# cc1110.net
KiCad netlist of a schematic drawn in Altium Designer
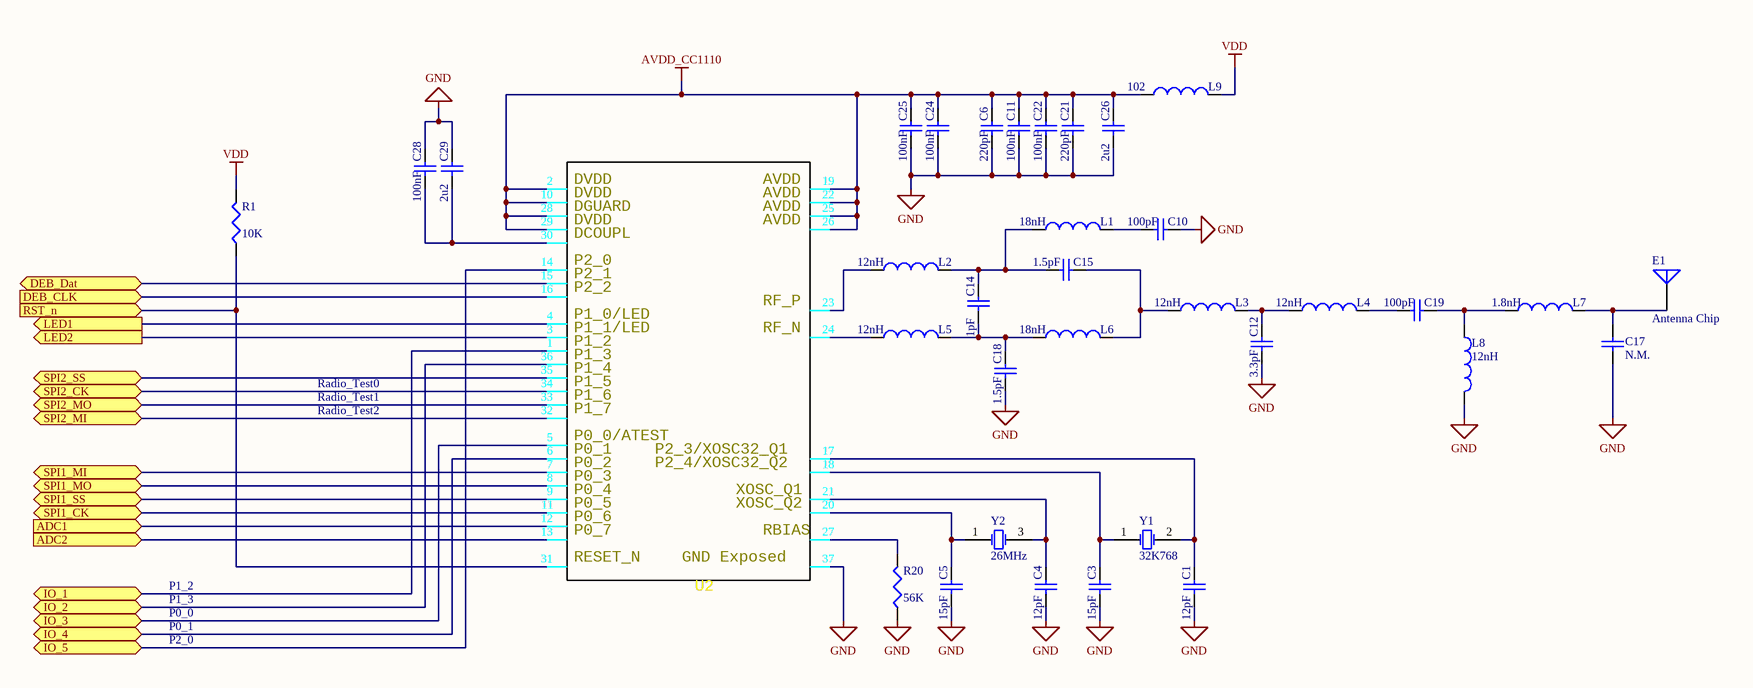
[diagram p0: cc1110.SchDoc]

(export (version "E")
  (design (tool "Eeschema 10.0.6"))
  (components
    (comp (ref "C1")
      (value "12pF")
      (footprint "0402")
      (description "Capacitor")
      (fields
        (field (name "MANUFACTURER") "FARNELL")
        (field (name "Comment") "Cap")
        (field (name "PUBLISHER") "Altium Limited")
      )
      (libsource (lib "Miscellaneous Devices") (part "Cap"))
    )
    (comp (ref "C3")
      (value "15pF")
      (footprint "0402")
      (description "Capacitor")
      (fields
        (field (name "MANUFACTURER") "FARNELL")
        (field (name "Comment") "Cap")
        (field (name "PUBLISHER") "Altium Limited")
      )
      (libsource (lib "Miscellaneous Devices") (part "Cap"))
    )
    (comp (ref "C4")
      (value "12pF")
      (footprint "0402")
      (description "Capacitor")
      (fields
        (field (name "MANUFACTURER") "FARNELL")
        (field (name "Comment") "Cap")
        (field (name "PUBLISHER") "Altium Limited")
      )
      (libsource (lib "Miscellaneous Devices") (part "Cap"))
    )
    (comp (ref "C5")
      (value "15pF")
      (footprint "0402")
      (description "Capacitor")
      (fields
        (field (name "MANUFACTURER") "FARNELL")
        (field (name "Comment") "Cap")
        (field (name "PUBLISHER") "Altium Limited")
      )
      (libsource (lib "Miscellaneous Devices") (part "Cap"))
    )
    (comp (ref "C6")
      (value "220pF")
      (footprint "0402")
      (description "Capacitor")
      (fields
        (field (name "MANUFACTURER") "FARNELL")
        (field (name "Comment") "Cap")
        (field (name "PUBLISHER") "Altium Limited")
      )
      (libsource (lib "Miscellaneous Devices") (part "Cap"))
    )
    (comp (ref "C10")
      (value "100pF")
      (footprint "0402")
      (description "Capacitor")
      (fields
        (field (name "MANUFACTURER") "FARNELL")
        (field (name "Comment") "Cap")
        (field (name "PUBLISHER") "Altium Limited")
      )
      (libsource (lib "Miscellaneous Devices") (part "Cap"))
    )
    (comp (ref "C11")
      (value "100nF")
      (footprint "0402")
      (description "Capacitor")
      (fields
        (field (name "MANUFACTURER") "FARNELL")
        (field (name "Comment") "Cap")
        (field (name "PUBLISHER") "Altium Limited")
      )
      (libsource (lib "Miscellaneous Devices") (part "Cap"))
    )
    (comp (ref "C12")
      (value "3.3pF")
      (footprint "0402")
      (description "Capacitor")
      (fields
        (field (name "MANUFACTURER") "FARNELL")
        (field (name "Comment") "Cap")
        (field (name "PUBLISHER") "Altium Limited")
      )
      (libsource (lib "Miscellaneous Devices") (part "Cap"))
    )
    (comp (ref "C14")
      (value "1pF")
      (footprint "0402")
      (description "Capacitor")
      (fields
        (field (name "MANUFACTURER") "FARNELL")
        (field (name "Comment") "Cap")
        (field (name "PUBLISHER") "Altium Limited")
      )
      (libsource (lib "Miscellaneous Devices") (part "Cap"))
    )
    (comp (ref "C15")
      (value "1.5pF")
      (footprint "0402")
      (description "Capacitor")
      (fields
        (field (name "MANUFACTURER") "FARNELL")
        (field (name "Comment") "Cap")
        (field (name "PUBLISHER") "Altium Limited")
      )
      (libsource (lib "Miscellaneous Devices") (part "Cap"))
    )
    (comp (ref "C17")
      (value "N.M.")
      (footprint "0402")
      (description "Capacitor")
      (fields (field (name "Comment") "Cap") (field (name "PUBLISHER") "Altium Limited"))
      (libsource (lib "Miscellaneous Devices") (part "Cap"))
    )
    (comp (ref "C18")
      (value "1.5pF")
      (footprint "0402")
      (description "Capacitor")
      (fields
        (field (name "MANUFACTURER") "FARNELL")
        (field (name "Comment") "Cap")
        (field (name "PUBLISHER") "Altium Limited")
      )
      (libsource (lib "Miscellaneous Devices") (part "Cap"))
    )
    (comp (ref "C19")
      (value "100pF")
      (footprint "0402")
      (description "Capacitor")
      (fields
        (field (name "MANUFACTURER") "FARNELL")
        (field (name "Comment") "Cap")
        (field (name "PUBLISHER") "Altium Limited")
      )
      (libsource (lib "Miscellaneous Devices") (part "Cap"))
    )
    (comp (ref "C21")
      (value "220pF")
      (footprint "0402")
      (description "Capacitor")
      (fields
        (field (name "MANUFACTURER") "FARNELL")
        (field (name "Comment") "Cap")
        (field (name "PUBLISHER") "Altium Limited")
      )
      (libsource (lib "Miscellaneous Devices") (part "Cap"))
    )
    (comp (ref "C22")
      (value "100nF")
      (footprint "0402")
      (description "Capacitor")
      (fields
        (field (name "MANUFACTURER") "FARNELL")
        (field (name "Comment") "Cap")
        (field (name "PUBLISHER") "Altium Limited")
      )
      (libsource (lib "Miscellaneous Devices") (part "Cap"))
    )
    (comp (ref "C24")
      (value "100nF")
      (footprint "0402")
      (description "Capacitor")
      (fields
        (field (name "MANUFACTURER") "FARNELL")
        (field (name "Comment") "Cap")
        (field (name "PUBLISHER") "Altium Limited")
      )
      (libsource (lib "Miscellaneous Devices") (part "Cap"))
    )
    (comp (ref "C25")
      (value "100nF")
      (footprint "0402")
      (description "Capacitor")
      (fields
        (field (name "MANUFACTURER") "FARNELL")
        (field (name "Comment") "Cap")
        (field (name "PUBLISHER") "Altium Limited")
      )
      (libsource (lib "Miscellaneous Devices") (part "Cap"))
    )
    (comp (ref "C26")
      (value "2u2")
      (footprint "C0805")
      (description "Capacitor")
      (fields
        (field (name "MANUFACTURER") "FARNELL")
        (field (name "Comment") "Cap")
        (field (name "PUBLISHER") "Altium Limited")
      )
      (libsource (lib "Miscellaneous Devices") (part "Cap"))
    )
    (comp (ref "C28")
      (value "100nF")
      (footprint "0402")
      (description "Capacitor")
      (fields
        (field (name "MANUFACTURER") "FARNELL")
        (field (name "Comment") "Cap")
        (field (name "PUBLISHER") "Altium Limited")
      )
      (libsource (lib "Miscellaneous Devices") (part "Cap"))
    )
    (comp (ref "C29")
      (value "2u2")
      (footprint "C0805")
      (description "Capacitor")
      (fields
        (field (name "MANUFACTURER") "FARNELL")
        (field (name "Comment") "Cap")
        (field (name "PUBLISHER") "Altium Limited")
      )
      (libsource (lib "Miscellaneous Devices") (part "Cap"))
    )
    (comp (ref "E1")
      (value "Antenna Chip")
      (footprint "Johanson_0868AT43A0020")
      (description "Generic Antenna")
      (fields (field (name "MANUFACTURER") "FARNELL") (field (name "PUBLISHER") "Altium Limited"))
      (libsource (lib "Miscellaneous Devices") (part "Antenna"))
    )
    (comp (ref "L1")
      (value "18nH")
      (footprint "0402-A")
      (description "Inductor")
      (fields (field (name "MANUFACTURER") "FARNELL") (field (name "PUBLISHER") "Altium Limited"))
      (libsource (lib "Miscellaneous Devices") (part "Inductor"))
    )
    (comp (ref "L2")
      (value "12nH")
      (footprint "0402-A")
      (description "Inductor")
      (fields (field (name "MANUFACTURER") "FARNELL") (field (name "PUBLISHER") "Altium Limited"))
      (libsource (lib "Miscellaneous Devices") (part "Inductor"))
    )
    (comp (ref "L3")
      (value "12nH")
      (footprint "0402-A")
      (description "Inductor")
      (fields (field (name "MANUFACTURER") "FARNELL") (field (name "PUBLISHER") "Altium Limited"))
      (libsource (lib "Miscellaneous Devices") (part "Inductor"))
    )
    (comp (ref "L4")
      (value "12nH")
      (footprint "0402-A")
      (description "Inductor")
      (fields (field (name "MANUFACTURER") "FARNELL") (field (name "PUBLISHER") "Altium Limited"))
      (libsource (lib "Miscellaneous Devices") (part "Inductor"))
    )
    (comp (ref "L5")
      (value "12nH")
      (footprint "0402-A")
      (description "Inductor")
      (fields (field (name "MANUFACTURER") "FARNELL") (field (name "PUBLISHER") "Altium Limited"))
      (libsource (lib "Miscellaneous Devices") (part "Inductor"))
    )
    (comp (ref "L6")
      (value "18nH")
      (footprint "0402-A")
      (description "Inductor")
      (fields (field (name "MANUFACTURER") "FARNELL") (field (name "PUBLISHER") "Altium Limited"))
      (libsource (lib "Miscellaneous Devices") (part "Inductor"))
    )
    (comp (ref "L7")
      (value "1.8nH")
      (footprint "0402-A")
      (description "Inductor")
      (fields (field (name "MANUFACTURER") "FARNELL") (field (name "PUBLISHER") "Altium Limited"))
      (libsource (lib "Miscellaneous Devices") (part "Inductor"))
    )
    (comp (ref "L8")
      (value "12nH")
      (footprint "0402-A")
      (description "Inductor")
      (fields (field (name "MANUFACTURER") "FARNELL") (field (name "PUBLISHER") "Altium Limited"))
      (libsource (lib "Miscellaneous Devices") (part "Inductor"))
    )
    (comp (ref "L9")
      (value "102")
      (footprint "0402-A")
      (description "Inductor")
      (fields (field (name "MANUFACTURER") "FARNELL") (field (name "PUBLISHER") "Altium Limited"))
      (libsource (lib "Miscellaneous Devices") (part "Inductor"))
    )
    (comp (ref "R1")
      (value "10K")
      (footprint "J1-0603")
      (description "Resistor")
      (fields
        (field (name "MANUFACTURER") "FARNELL")
        (field (name "Comment") "Res3")
        (field (name "PUBLISHER") "Altium Limited")
      )
      (libsource (lib "Miscellaneous Devices") (part "Res3"))
    )
    (comp (ref "R20")
      (value "56K")
      (footprint "J1-0603")
      (description "Resistor")
      (fields
        (field (name "MANUFACTURER") "FARNELL")
        (field (name "Comment") "Res3")
        (field (name "PUBLISHER") "Altium Limited")
      )
      (libsource (lib "Miscellaneous Devices") (part "Res3"))
    )
    (comp (ref "U2")
      (value "CC1110")
      (footprint "QLP36_4_4 (Reflow)")
      (description "Single chip transceiver")
      (fields (field (name "MANUFACTURER") "FARNELL"))
      (libsource (lib "mdap") (part "CC1110"))
    )
    (comp (ref "Y1")
      (value "32K768")
      (footprint "xtal_3215")
      (description "Crystal Oscillator")
      (fields (field (name "MANUFACTURER") "Smart Prototyping"))
      (libsource (lib "Miscellaneous Devices") (part "XTAL"))
    )
    (comp (ref "Y2")
      (value "26MHz")
      (footprint "xtal_3225")
      (description "Crystal Oscillator")
      (fields (field (name "MANUFACTURER") "Smart Prototyping"))
      (libsource (lib "MDAP") (part "XTAL_4"))
    )
  )
  (nets
    (net (code "1") (name "/ADC1") (class "Default") (node (ref "U2") (pin "12") (pintype "passive")))
    (net (code "2") (name "/ADC2") (class "Default") (node (ref "U2") (pin "13") (pintype "passive")))
    (net (code "3") (name "/DEB_CLK") (class "Default") (node (ref "U2") (pin "16") (pintype "passive")))
    (net (code "4") (name "/DEB_Dat") (class "Default") (node (ref "U2") (pin "15") (pintype "passive")))
    (net (code "5") (name "/IO_1") (class "Default") (node (ref "U2") (pin "1") (pintype "passive")))
    (net (code "6") (name "/IO_2") (class "Default") (node (ref "U2") (pin "36") (pintype "passive")))
    (net (code "7") (name "/IO_3") (class "Default") (node (ref "U2") (pin "5") (pintype "passive")))
    (net (code "8") (name "/IO_4") (class "Default") (node (ref "U2") (pin "6") (pintype "passive")))
    (net (code "9") (name "/IO_5") (class "Default") (node (ref "U2") (pin "14") (pintype "passive")))
    (net (code "10") (name "/LED1") (class "Default") (node (ref "U2") (pin "4") (pintype "passive")))
    (net (code "11") (name "/LED2") (class "Default") (node (ref "U2") (pin "3") (pintype "passive")))
    (net (code "12") (name "/RST_n") (class "Default")
      (node (ref "R1") (pin "1") (pinfunction "1_1") (pintype "passive"))
      (node (ref "U2") (pin "31") (pintype "passive"))
    )
    (net (code "13") (name "/SPI1_CK") (class "Default") (node (ref "U2") (pin "11") (pintype "passive")))
    (net (code "14") (name "/SPI1_MI") (class "Default") (node (ref "U2") (pin "7") (pintype "passive")))
    (net (code "15") (name "/SPI1_MO") (class "Default") (node (ref "U2") (pin "8") (pintype "passive")))
    (net (code "16") (name "/SPI1_SS") (class "Default") (node (ref "U2") (pin "9") (pintype "passive")))
    (net (code "17") (name "/SPI2_CK") (class "Default") (node (ref "U2") (pin "34") (pintype "passive")))
    (net (code "18") (name "/SPI2_MI") (class "Default") (node (ref "U2") (pin "32") (pintype "passive")))
    (net (code "19") (name "/SPI2_MO") (class "Default") (node (ref "U2") (pin "33") (pintype "passive")))
    (net (code "20") (name "/SPI2_SS") (class "Default") (node (ref "U2") (pin "35") (pintype "passive")))
    (net (code "21") (name "AVDD_CC1110") (class "Default")
      (node (ref "C11") (pin "2") (pinfunction "2_2") (pintype "passive"))
      (node (ref "C21") (pin "2") (pinfunction "2_2") (pintype "passive"))
      (node (ref "C22") (pin "2") (pinfunction "2_2") (pintype "passive"))
      (node (ref "C24") (pin "2") (pinfunction "2_2") (pintype "passive"))
      (node (ref "C25") (pin "2") (pinfunction "2_2") (pintype "passive"))
      (node (ref "C26") (pin "2") (pinfunction "2_2") (pintype "passive"))
      (node (ref "C6") (pin "2") (pinfunction "2_2") (pintype "passive"))
      (node (ref "L9") (pin "1") (pinfunction "1_1") (pintype "passive"))
      (node (ref "U2") (pin "10") (pintype "passive"))
      (node (ref "U2") (pin "19") (pintype "passive"))
      (node (ref "U2") (pin "2") (pintype "passive"))
      (node (ref "U2") (pin "22") (pintype "passive"))
      (node (ref "U2") (pin "25") (pintype "passive"))
      (node (ref "U2") (pin "26") (pintype "passive"))
      (node (ref "U2") (pin "28") (pintype "passive"))
      (node (ref "U2") (pin "29") (pintype "passive"))
    )
    (net (code "22") (name "GND") (class "Default")
      (node (ref "C1") (pin "1") (pinfunction "1_1") (pintype "passive"))
      (node (ref "C10") (pin "1") (pinfunction "1_1") (pintype "passive"))
      (node (ref "C11") (pin "1") (pinfunction "1_1") (pintype "passive"))
      (node (ref "C12") (pin "1") (pinfunction "1_1") (pintype "passive"))
      (node (ref "C17") (pin "2") (pinfunction "2_2") (pintype "passive"))
      (node (ref "C18") (pin "1") (pinfunction "1_1") (pintype "passive"))
      (node (ref "C21") (pin "1") (pinfunction "1_1") (pintype "passive"))
      (node (ref "C22") (pin "1") (pinfunction "1_1") (pintype "passive"))
      (node (ref "C24") (pin "1") (pinfunction "1_1") (pintype "passive"))
      (node (ref "C25") (pin "1") (pinfunction "1_1") (pintype "passive"))
      (node (ref "C26") (pin "1") (pinfunction "1_1") (pintype "passive"))
      (node (ref "C28") (pin "2") (pinfunction "2_2") (pintype "passive"))
      (node (ref "C29") (pin "2") (pinfunction "2_2") (pintype "passive"))
      (node (ref "C3") (pin "1") (pinfunction "1_1") (pintype "passive"))
      (node (ref "C4") (pin "1") (pinfunction "1_1") (pintype "passive"))
      (node (ref "C5") (pin "1") (pinfunction "1_1") (pintype "passive"))
      (node (ref "C6") (pin "1") (pinfunction "1_1") (pintype "passive"))
      (node (ref "L8") (pin "2") (pinfunction "2_2") (pintype "passive"))
      (node (ref "R20") (pin "1") (pinfunction "1_1") (pintype "passive"))
      (node (ref "U2") (pin "37") (pintype "passive"))
    )
    (net (code "23") (name "Net-(C10-Pad2)") (class "Default")
      (node (ref "C10") (pin "2") (pinfunction "2_2") (pintype "passive"))
      (node (ref "L1") (pin "2") (pinfunction "2_2") (pintype "passive"))
    )
    (net (code "24") (name "Net-(C12-Pad2)") (class "Default")
      (node (ref "C12") (pin "2") (pinfunction "2_2") (pintype "passive"))
      (node (ref "L3") (pin "2") (pinfunction "2_2") (pintype "passive"))
      (node (ref "L4") (pin "1") (pinfunction "1_1") (pintype "passive"))
    )
    (net (code "25") (name "Net-(C14-Pad1)") (class "Default")
      (node (ref "C14") (pin "1") (pinfunction "1_1") (pintype "passive"))
      (node (ref "C18") (pin "2") (pinfunction "2_2") (pintype "passive"))
      (node (ref "L5") (pin "2") (pinfunction "2_2") (pintype "passive"))
      (node (ref "L6") (pin "1") (pinfunction "1_1") (pintype "passive"))
    )
    (net (code "26") (name "Net-(C14-Pad2)") (class "Default")
      (node (ref "C14") (pin "2") (pinfunction "2_2") (pintype "passive"))
      (node (ref "C15") (pin "2") (pinfunction "2_2") (pintype "passive"))
      (node (ref "L1") (pin "1") (pinfunction "1_1") (pintype "passive"))
      (node (ref "L2") (pin "2") (pinfunction "2_2") (pintype "passive"))
    )
    (net (code "27") (name "Net-(C15-Pad1)") (class "Default")
      (node (ref "C15") (pin "1") (pinfunction "1_1") (pintype "passive"))
      (node (ref "L3") (pin "1") (pinfunction "1_1") (pintype "passive"))
      (node (ref "L6") (pin "2") (pinfunction "2_2") (pintype "passive"))
    )
    (net (code "28") (name "Net-(C19-Pad1)") (class "Default")
      (node (ref "C19") (pin "1") (pinfunction "1_1") (pintype "passive"))
      (node (ref "L7") (pin "1") (pinfunction "1_1") (pintype "passive"))
      (node (ref "L8") (pin "1") (pinfunction "1_1") (pintype "passive"))
    )
    (net (code "29") (name "Net-(C19-Pad2)") (class "Default")
      (node (ref "C19") (pin "2") (pinfunction "2_2") (pintype "passive"))
      (node (ref "L4") (pin "2") (pinfunction "2_2") (pintype "passive"))
    )
    (net (code "30") (name "Net-(C28-Pad1)") (class "Default")
      (node (ref "C28") (pin "1") (pinfunction "1_1") (pintype "passive"))
      (node (ref "C29") (pin "1") (pinfunction "1_1") (pintype "passive"))
      (node (ref "U2") (pin "30") (pintype "passive"))
    )
    (net (code "31") (name "Net-(E1-A)") (class "Default")
      (node (ref "C17") (pin "1") (pinfunction "1_1") (pintype "passive"))
      (node (ref "E1") (pin "1") (pinfunction "A_1") (pintype "passive"))
      (node (ref "L7") (pin "2") (pinfunction "2_2") (pintype "passive"))
    )
    (net (code "32") (name "Net-(L2-Pad1)") (class "Default")
      (node (ref "L2") (pin "1") (pinfunction "1_1") (pintype "passive"))
      (node (ref "U2") (pin "23") (pintype "passive"))
    )
    (net (code "33") (name "Net-(L5-Pad1)") (class "Default")
      (node (ref "L5") (pin "1") (pinfunction "1_1") (pintype "passive"))
      (node (ref "U2") (pin "24") (pintype "passive"))
    )
    (net (code "34") (name "Net-(R20-Pad2)") (class "Default")
      (node (ref "R20") (pin "2") (pinfunction "2_2") (pintype "passive"))
      (node (ref "U2") (pin "27") (pintype "passive"))
    )
    (net (code "35") (name "Net-(Y1-OSC1)") (class "Default")
      (node (ref "C3") (pin "2") (pinfunction "2_2") (pintype "passive"))
      (node (ref "U2") (pin "18") (pintype "passive"))
      (node (ref "Y1") (pin "1") (pinfunction "OSC1_1") (pintype "passive"))
    )
    (net (code "36") (name "Net-(Y1-OSC2)") (class "Default")
      (node (ref "C1") (pin "2") (pinfunction "2_2") (pintype "passive"))
      (node (ref "U2") (pin "17") (pintype "passive"))
      (node (ref "Y1") (pin "2") (pinfunction "OSC2_2") (pintype "passive"))
    )
    (net (code "37") (name "Net-(Y2-OSC1)") (class "Default")
      (node (ref "C5") (pin "2") (pinfunction "2_2") (pintype "passive"))
      (node (ref "U2") (pin "20") (pintype "passive"))
      (node (ref "Y2") (pin "1") (pinfunction "OSC1_1") (pintype "passive"))
    )
    (net (code "38") (name "Net-(Y2-OSC2)") (class "Default")
      (node (ref "C4") (pin "2") (pinfunction "2_2") (pintype "passive"))
      (node (ref "U2") (pin "21") (pintype "passive"))
      (node (ref "Y2") (pin "3") (pinfunction "OSC2_3") (pintype "passive"))
    )
    (net (code "39") (name "VDD") (class "Default")
      (node (ref "L9") (pin "2") (pinfunction "2_2") (pintype "passive"))
      (node (ref "R1") (pin "2") (pinfunction "2_2") (pintype "passive"))
    )
  )
)
